# 4ch_GRT_reader.net
KiCad netlist of a schematic drawn in Altium Designer
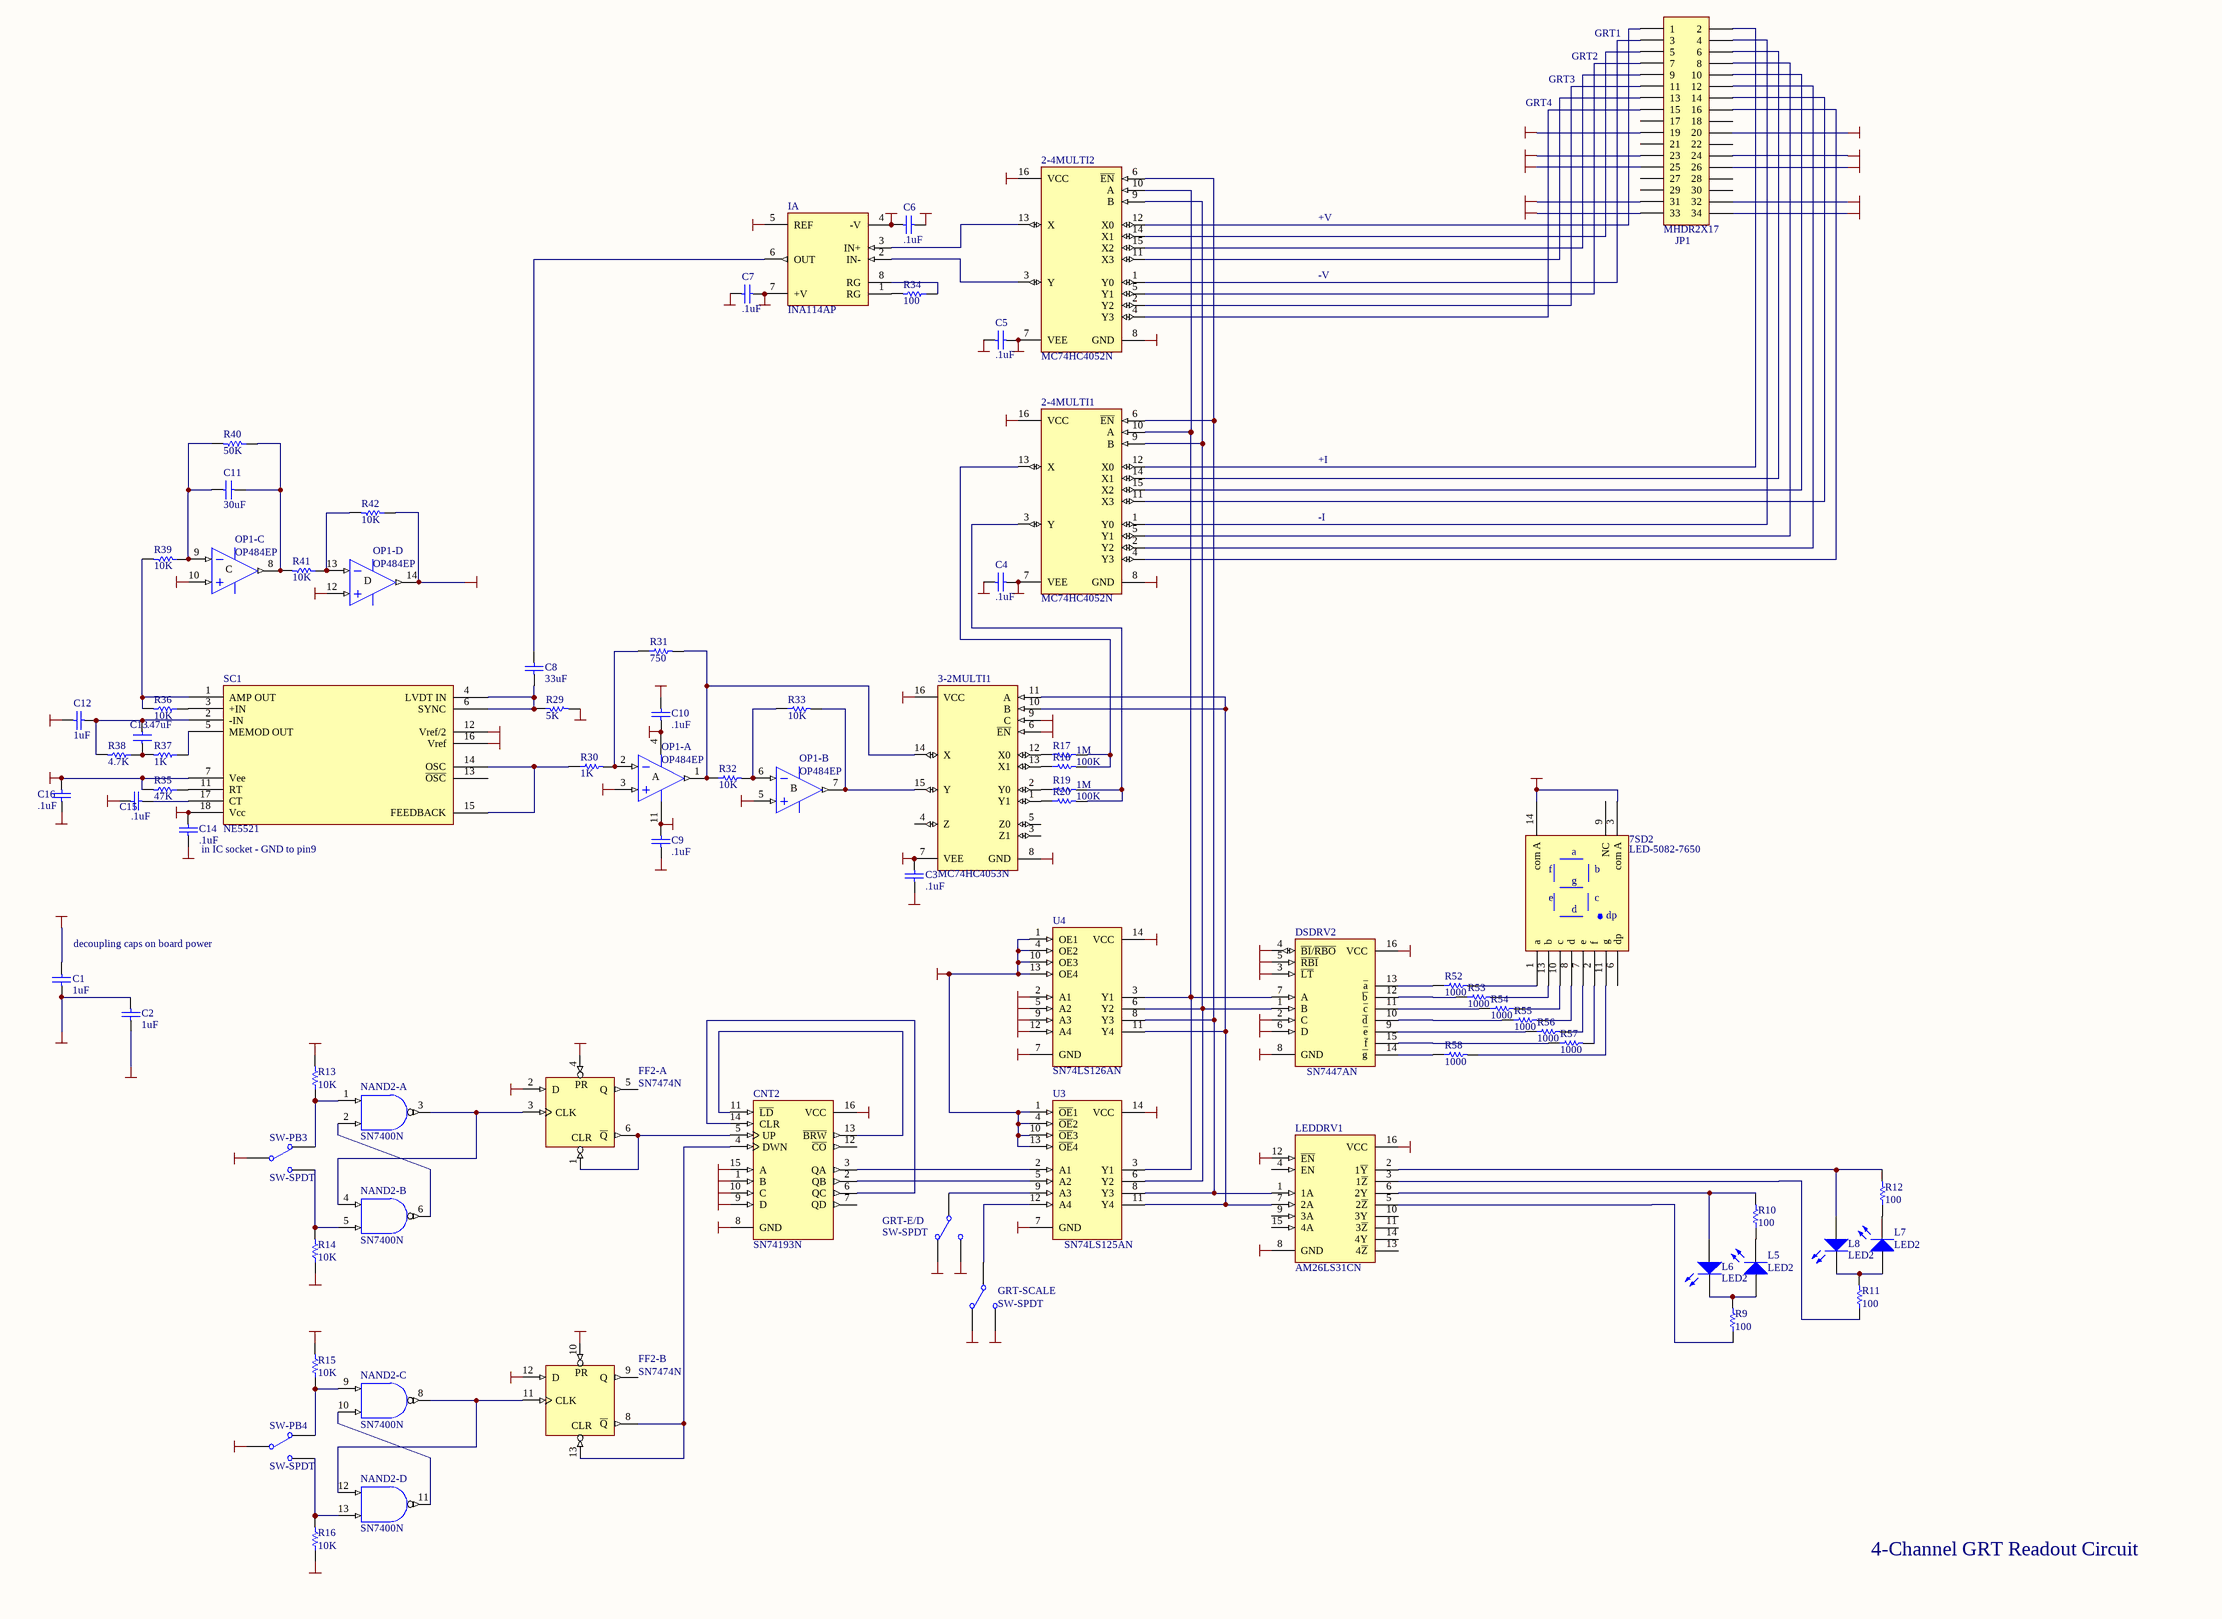
[diagram p0: 4ch GRT reader.SchDoc]

(export (version "E")
  (design (tool "Eeschema 10.0.6"))
  (components
    (comp (ref "2-4MULTI1")
      (value "MC74HC4052N")
      (footprint "DIP-16/X1.5")
      (description "Dual 4-Channel Analog Multiplexer/Demultiplexer")
      (fields (field (name "MANUFACTURER") "ON Semiconductor"))
      (libsource (lib "ON Semi Logic Multiplexer") (part "MC74HC4052N"))
    )
    (comp (ref "2-4MULTI2")
      (value "MC74HC4052N")
      (footprint "DIP-16/X1.5")
      (description "Dual 4-Channel Analog Multiplexer/Demultiplexer")
      (fields (field (name "MANUFACTURER") "ON Semiconductor"))
      (libsource (lib "ON Semi Logic Multiplexer") (part "MC74HC4052N"))
    )
    (comp (ref "3-2MULTI1")
      (value "MC74HC4053N")
      (footprint "DIP-16/X1.5")
      (description "Analog Multiplexer/Demultiplexer")
      (fields (field (name "MANUFACTURER") "ON Semiconductor"))
      (libsource (lib "ON Semi Logic Multiplexer") (part "MC74HC4053N"))
    )
    (comp (ref "7SD2")
      (value "LED-5082-7650")
      (footprint "DIP-14")
      (libsource (lib "Steves Integrated Library1") (part "LED-5082-7650"))
    )
    (comp (ref "C1")
      (value "1uF")
      (footprint "RAD-0.2")
      (description "Capacitor")
      (fields (field (name "MANUFACTURER") "Generic Components") (field (name "ALTIUM_VALUE") "1uF"))
      (libsource (lib "Miscellaneous Devices") (part "Cap"))
    )
    (comp (ref "C2")
      (value "1uF")
      (footprint "RAD-0.2")
      (description "Capacitor")
      (fields (field (name "MANUFACTURER") "Generic Components") (field (name "ALTIUM_VALUE") "1uF"))
      (libsource (lib "Miscellaneous Devices") (part "Cap"))
    )
    (comp (ref "C3")
      (value ".1uF")
      (footprint "RAD-0.1")
      (description "Capacitor")
      (fields (field (name "MANUFACTURER") "Generic Components") (field (name "ALTIUM_VALUE") ".1uF"))
      (libsource (lib "Miscellaneous Devices") (part "Cap"))
    )
    (comp (ref "C4")
      (value ".1uF")
      (footprint "RAD-0.1")
      (description "Capacitor")
      (fields (field (name "MANUFACTURER") "Generic Components") (field (name "ALTIUM_VALUE") ".1uF"))
      (libsource (lib "Miscellaneous Devices") (part "Cap"))
    )
    (comp (ref "C5")
      (value ".1uF")
      (footprint "RAD-0.1")
      (description "Capacitor")
      (fields (field (name "MANUFACTURER") "Generic Components") (field (name "ALTIUM_VALUE") ".1uF"))
      (libsource (lib "Miscellaneous Devices") (part "Cap"))
    )
    (comp (ref "C6")
      (value ".1uF")
      (footprint "RAD-0.1")
      (description "Capacitor")
      (fields (field (name "MANUFACTURER") "Generic Components") (field (name "ALTIUM_VALUE") ".1uF"))
      (libsource (lib "Miscellaneous Devices") (part "Cap"))
    )
    (comp (ref "C7")
      (value ".1uF")
      (footprint "RAD-0.1")
      (description "Capacitor")
      (fields (field (name "MANUFACTURER") "Generic Components") (field (name "ALTIUM_VALUE") ".1uF"))
      (libsource (lib "Miscellaneous Devices") (part "Cap"))
    )
    (comp (ref "C8")
      (value "33uF")
      (footprint "RAD-0.1")
      (description "Capacitor")
      (fields (field (name "MANUFACTURER") "Generic Components") (field (name "ALTIUM_VALUE") "33uF"))
      (libsource (lib "Miscellaneous Devices") (part "Cap"))
    )
    (comp (ref "C9")
      (value ".1uF")
      (footprint "RAD-0.1")
      (description "Capacitor")
      (fields (field (name "MANUFACTURER") "Generic Components") (field (name "ALTIUM_VALUE") ".1uF"))
      (libsource (lib "Miscellaneous Devices") (part "Cap"))
    )
    (comp (ref "C10")
      (value ".1uF")
      (footprint "RAD-0.1")
      (description "Capacitor")
      (fields (field (name "MANUFACTURER") "Generic Components") (field (name "ALTIUM_VALUE") ".1uF"))
      (libsource (lib "Miscellaneous Devices") (part "Cap"))
    )
    (comp (ref "C11")
      (value "30uF")
      (footprint "RAD-0.1")
      (description "Capacitor")
      (fields (field (name "MANUFACTURER") "Generic Components") (field (name "ALTIUM_VALUE") "30uF"))
      (libsource (lib "Miscellaneous Devices") (part "Cap"))
    )
    (comp (ref "C12")
      (value "1uF")
      (footprint "RAD-0.1")
      (description "Capacitor")
      (fields (field (name "MANUFACTURER") "Generic Components") (field (name "ALTIUM_VALUE") "1uF"))
      (libsource (lib "") (part "Cap_1"))
    )
    (comp (ref "C13")
      (value ".47uF")
      (footprint "RAD-0.1")
      (description "Capacitor")
      (fields (field (name "MANUFACTURER") "Generic Components") (field (name "ALTIUM_VALUE") ".47uF"))
      (libsource (lib "Miscellaneous Devices") (part "Cap"))
    )
    (comp (ref "C14")
      (value "in IC socket - GND to pin9")
      (footprint "RAD-0.1")
      (description "Capacitor")
      (fields (field (name "MANUFACTURER") "Generic Components") (field (name "ALTIUM_VALUE") ".1uF"))
      (libsource (lib "Miscellaneous Devices") (part "Cap"))
    )
    (comp (ref "C15")
      (value ".1uF")
      (footprint "RAD-0.1")
      (description "Capacitor")
      (fields (field (name "MANUFACTURER") "Generic Components") (field (name "ALTIUM_VALUE") ".1uF"))
      (libsource (lib "Miscellaneous Devices") (part "Cap"))
    )
    (comp (ref "C16")
      (value ".1uF")
      (footprint "RAD-0.1")
      (description "Capacitor")
      (fields (field (name "MANUFACTURER") "Generic Components") (field (name "ALTIUM_VALUE") ".1uF"))
      (libsource (lib "Miscellaneous Devices") (part "Cap"))
    )
    (comp (ref "CNT2")
      (value "SN74193N")
      (footprint "DIP-16/X1.5")
      (description "Synchronous 4-Bit Up/Down Counter (Dual Clock with Clear)")
      (fields (field (name "MANUFACTURER") "Texas Instruments"))
      (libsource (lib "TI Logic Counter") (part "SN74193N"))
    )
    (comp (ref "DSDRV2")
      (value "SN7447AN")
      (footprint "DIP-16/X1.5")
      (description "BCD-to-Seven-Segment Decoder/Driver")
      (fields (field (name "MANUFACTURER") "Texas Instruments"))
      (libsource (lib "TI Interface Display Driver") (part "SN7447AN"))
    )
    (comp (ref "FF2-")
      (value "SN7474N")
      (footprint "DIP-14/D19.7")
      (description "Dual D-Type Positive-Edge-Triggered Flip-Flop with Preset and Clear")
      (fields (field (name "MANUFACTURER") "Texas Instruments"))
      (libsource (lib "TI Logic Flip-Flop") (part "SN7474N"))
    )
    (comp (ref "GRT-E/D")
      (value "SW-SPDT")
      (footprint "SPDT-3")
      (description "Single-Pole, Double-Throw Switch")
      (fields (field (name "MANUFACTURER") "Generic Components"))
      (libsource (lib "Miscellaneous Devices") (part "SW-SPDT"))
    )
    (comp (ref "GRT-SCALE")
      (value "SW-SPDT")
      (footprint "SPDT-3")
      (description "Single-Pole, Double-Throw Switch")
      (fields (field (name "MANUFACTURER") "Generic Components"))
      (libsource (lib "Miscellaneous Devices") (part "SW-SPDT"))
    )
    (comp (ref "IA")
      (value "INA114AP")
      (footprint "DIP-8")
      (description "Precision Instrumentation Amplifier")
      (fields (field (name "MANUFACTURER") "Burr-Brown"))
      (libsource (lib "BB Instrumentation Amplifier") (part "INA114AP"))
    )
    (comp (ref "JP1")
      (value "MHDR2X17")
      (footprint "HDR2X17")
      (description "Header, 17-Pin, Dual row")
      (fields (field (name "MANUFACTURER") "Generic Components"))
      (libsource (lib "Miscellaneous Connectors") (part "MHDR2X17"))
    )
    (comp (ref "L5")
      (value "LED2")
      (footprint "HDR1X2")
      (description "Typical RED, GREEN, YELLOW, AMBER GaAs LED")
      (fields (field (name "MANUFACTURER") "Generic Components"))
      (libsource (lib "Miscellaneous Devices") (part "LED2"))
    )
    (comp (ref "L6")
      (value "LED2")
      (footprint "HDR1X2")
      (description "Typical RED, GREEN, YELLOW, AMBER GaAs LED")
      (fields (field (name "MANUFACTURER") "Generic Components"))
      (libsource (lib "Miscellaneous Devices") (part "LED2"))
    )
    (comp (ref "L7")
      (value "LED2")
      (footprint "HDR1X2")
      (description "Typical RED, GREEN, YELLOW, AMBER GaAs LED")
      (fields (field (name "MANUFACTURER") "Generic Components"))
      (libsource (lib "Miscellaneous Devices") (part "LED2"))
    )
    (comp (ref "L8")
      (value "LED2")
      (footprint "HDR1X2")
      (description "Typical RED, GREEN, YELLOW, AMBER GaAs LED")
      (fields (field (name "MANUFACTURER") "Generic Components"))
      (libsource (lib "Miscellaneous Devices") (part "LED2"))
    )
    (comp (ref "LEDDRV1")
      (value "AM26LS31CN")
      (footprint "DIP-16/X1.5")
      (description "Quadruple Differential Line Driver")
      (fields (field (name "MANUFACTURER") "Texas Instruments"))
      (libsource (lib "TI Interface Line Driver") (part "AM26LS31CN"))
    )
    (comp (ref "NAND2-")
      (value "SN7400N")
      (footprint "DIP-14/D19.7")
      (description "Quadruple 2-Input Positive-NAND Gate")
      (fields (field (name "MANUFACTURER") "Texas Instruments"))
      (libsource (lib "TI Logic Gate 1") (part "SN7400N"))
    )
    (comp (ref "OP1-")
      (value "OP484EP")
      (footprint "DIP-14")
      (description "Precision Rail-to-Rail Input and Output Operational Amplifier")
      (fields (field (name "MANUFACTURER") "Analog Devices"))
      (libsource (lib "AD Operational Amplifier") (part "OP484EP"))
    )
    (comp (ref "R9")
      (value "100")
      (footprint "AXIAL-0.3")
      (description "Resistor")
      (fields (field (name "MANUFACTURER") "Generic Components") (field (name "ALTIUM_VALUE") "100"))
      (libsource (lib "Miscellaneous Devices") (part "Res1"))
    )
    (comp (ref "R10")
      (value "100")
      (footprint "AXIAL-0.3")
      (description "Resistor")
      (fields (field (name "MANUFACTURER") "Generic Components") (field (name "ALTIUM_VALUE") "100"))
      (libsource (lib "Miscellaneous Devices") (part "Res1"))
    )
    (comp (ref "R11")
      (value "100")
      (footprint "AXIAL-0.3")
      (description "Resistor")
      (fields (field (name "MANUFACTURER") "Generic Components") (field (name "ALTIUM_VALUE") "100"))
      (libsource (lib "Miscellaneous Devices") (part "Res1"))
    )
    (comp (ref "R12")
      (value "100")
      (footprint "AXIAL-0.3")
      (description "Resistor")
      (fields (field (name "MANUFACTURER") "Generic Components") (field (name "ALTIUM_VALUE") "100"))
      (libsource (lib "Miscellaneous Devices") (part "Res1"))
    )
    (comp (ref "R13")
      (value "10K")
      (footprint "AXIAL-0.3")
      (description "Resistor")
      (fields (field (name "MANUFACTURER") "Generic Components") (field (name "ALTIUM_VALUE") "10K"))
      (libsource (lib "Miscellaneous Devices") (part "Res1"))
    )
    (comp (ref "R14")
      (value "10K")
      (footprint "AXIAL-0.3")
      (description "Resistor")
      (fields (field (name "MANUFACTURER") "Generic Components") (field (name "ALTIUM_VALUE") "10K"))
      (libsource (lib "Miscellaneous Devices") (part "Res1"))
    )
    (comp (ref "R15")
      (value "10K")
      (footprint "AXIAL-0.3")
      (description "Resistor")
      (fields (field (name "MANUFACTURER") "Generic Components") (field (name "ALTIUM_VALUE") "10K"))
      (libsource (lib "Miscellaneous Devices") (part "Res1"))
    )
    (comp (ref "R16")
      (value "10K")
      (footprint "AXIAL-0.3")
      (description "Resistor")
      (fields (field (name "MANUFACTURER") "Generic Components") (field (name "ALTIUM_VALUE") "10K"))
      (libsource (lib "Miscellaneous Devices") (part "Res1"))
    )
    (comp (ref "R17")
      (value "1M")
      (footprint "AXIAL-0.3")
      (description "Resistor")
      (fields (field (name "MANUFACTURER") "Generic Components") (field (name "ALTIUM_VALUE") "1M"))
      (libsource (lib "Miscellaneous Devices") (part "Res1"))
    )
    (comp (ref "R18")
      (value "100K")
      (footprint "AXIAL-0.3")
      (description "Resistor")
      (fields (field (name "MANUFACTURER") "Generic Components") (field (name "ALTIUM_VALUE") "100K"))
      (libsource (lib "Miscellaneous Devices") (part "Res1"))
    )
    (comp (ref "R19")
      (value "1M")
      (footprint "AXIAL-0.3")
      (description "Resistor")
      (fields (field (name "MANUFACTURER") "Generic Components") (field (name "ALTIUM_VALUE") "1M"))
      (libsource (lib "Miscellaneous Devices") (part "Res1"))
    )
    (comp (ref "R20")
      (value "100K")
      (footprint "AXIAL-0.3")
      (description "Resistor")
      (fields (field (name "MANUFACTURER") "Generic Components") (field (name "ALTIUM_VALUE") "100K"))
      (libsource (lib "Miscellaneous Devices") (part "Res1"))
    )
    (comp (ref "R29")
      (value "5K")
      (footprint "AXIAL-0.3")
      (description "Resistor")
      (fields (field (name "MANUFACTURER") "Generic Components") (field (name "ALTIUM_VALUE") "5K"))
      (libsource (lib "") (part "Res1_1"))
    )
    (comp (ref "R30")
      (value "1K")
      (footprint "AXIAL-0.3")
      (description "Resistor")
      (fields (field (name "MANUFACTURER") "Generic Components") (field (name "ALTIUM_VALUE") "1K"))
      (libsource (lib "Miscellaneous Devices") (part "Res1"))
    )
    (comp (ref "R31")
      (value "750")
      (footprint "AXIAL-0.3")
      (description "Resistor")
      (fields (field (name "MANUFACTURER") "Generic Components") (field (name "ALTIUM_VALUE") "750"))
      (libsource (lib "Miscellaneous Devices") (part "Res1"))
    )
    (comp (ref "R32")
      (value "10K")
      (footprint "AXIAL-0.3")
      (description "Resistor")
      (fields (field (name "MANUFACTURER") "Generic Components") (field (name "ALTIUM_VALUE") "10K"))
      (libsource (lib "Miscellaneous Devices") (part "Res1"))
    )
    (comp (ref "R33")
      (value "10K")
      (footprint "AXIAL-0.3")
      (description "Resistor")
      (fields (field (name "MANUFACTURER") "Generic Components") (field (name "ALTIUM_VALUE") "10K"))
      (libsource (lib "Miscellaneous Devices") (part "Res1"))
    )
    (comp (ref "R34")
      (value "100")
      (footprint "AXIAL-0.3")
      (description "Resistor")
      (fields (field (name "MANUFACTURER") "Generic Components") (field (name "ALTIUM_VALUE") "100"))
      (libsource (lib "Miscellaneous Devices") (part "Res1"))
    )
    (comp (ref "R35")
      (value "47K")
      (footprint "AXIAL-0.3")
      (description "Resistor")
      (fields (field (name "MANUFACTURER") "Generic Components") (field (name "ALTIUM_VALUE") "47K"))
      (libsource (lib "Miscellaneous Devices") (part "Res1"))
    )
    (comp (ref "R36")
      (value "10K")
      (footprint "AXIAL-0.3")
      (description "Resistor")
      (fields (field (name "MANUFACTURER") "Generic Components") (field (name "ALTIUM_VALUE") "10K"))
      (libsource (lib "") (part "Res1_2"))
    )
    (comp (ref "R37")
      (value "1K")
      (footprint "AXIAL-0.3")
      (description "Resistor")
      (fields (field (name "MANUFACTURER") "Generic Components") (field (name "ALTIUM_VALUE") "1K"))
      (libsource (lib "") (part "Res1_2"))
    )
    (comp (ref "R38")
      (value "4.7K")
      (footprint "AXIAL-0.3")
      (description "Resistor")
      (fields (field (name "MANUFACTURER") "Generic Components") (field (name "ALTIUM_VALUE") "4.7K"))
      (libsource (lib "") (part "Res1_2"))
    )
    (comp (ref "R39")
      (value "10K")
      (footprint "AXIAL-0.3")
      (description "Resistor")
      (fields (field (name "MANUFACTURER") "Generic Components") (field (name "ALTIUM_VALUE") "10K"))
      (libsource (lib "") (part "Res1_2"))
    )
    (comp (ref "R40")
      (value "50K")
      (footprint "AXIAL-0.3")
      (description "Resistor")
      (fields (field (name "MANUFACTURER") "Generic Components") (field (name "ALTIUM_VALUE") "50K"))
      (libsource (lib "") (part "Res1_2"))
    )
    (comp (ref "R41")
      (value "10K")
      (footprint "AXIAL-0.3")
      (description "Resistor")
      (fields (field (name "MANUFACTURER") "Generic Components") (field (name "ALTIUM_VALUE") "10K"))
      (libsource (lib "") (part "Res1_2"))
    )
    (comp (ref "R42")
      (value "10K")
      (footprint "AXIAL-0.3")
      (description "Resistor")
      (fields (field (name "MANUFACTURER") "Generic Components") (field (name "ALTIUM_VALUE") "10K"))
      (libsource (lib "") (part "Res1_2"))
    )
    (comp (ref "R52")
      (value "1000")
      (footprint "AXIAL-0.3")
      (description "Resistor")
      (fields (field (name "MANUFACTURER") "Generic Components") (field (name "ALTIUM_VALUE") "1000"))
      (libsource (lib "Miscellaneous Devices") (part "Res1"))
    )
    (comp (ref "R53")
      (value "1000")
      (footprint "AXIAL-0.3")
      (description "Resistor")
      (fields (field (name "MANUFACTURER") "Generic Components") (field (name "ALTIUM_VALUE") "1000"))
      (libsource (lib "Miscellaneous Devices") (part "Res1"))
    )
    (comp (ref "R54")
      (value "1000")
      (footprint "AXIAL-0.3")
      (description "Resistor")
      (fields (field (name "MANUFACTURER") "Generic Components") (field (name "ALTIUM_VALUE") "1000"))
      (libsource (lib "Miscellaneous Devices") (part "Res1"))
    )
    (comp (ref "R55")
      (value "1000")
      (footprint "AXIAL-0.3")
      (description "Resistor")
      (fields (field (name "MANUFACTURER") "Generic Components") (field (name "ALTIUM_VALUE") "1000"))
      (libsource (lib "Miscellaneous Devices") (part "Res1"))
    )
    (comp (ref "R56")
      (value "1000")
      (footprint "AXIAL-0.3")
      (description "Resistor")
      (fields (field (name "MANUFACTURER") "Generic Components") (field (name "ALTIUM_VALUE") "1000"))
      (libsource (lib "Miscellaneous Devices") (part "Res1"))
    )
    (comp (ref "R57")
      (value "1000")
      (footprint "AXIAL-0.3")
      (description "Resistor")
      (fields (field (name "MANUFACTURER") "Generic Components") (field (name "ALTIUM_VALUE") "1000"))
      (libsource (lib "Miscellaneous Devices") (part "Res1"))
    )
    (comp (ref "R58")
      (value "1000")
      (footprint "AXIAL-0.3")
      (description "Resistor")
      (fields (field (name "MANUFACTURER") "Generic Components") (field (name "ALTIUM_VALUE") "1000"))
      (libsource (lib "Miscellaneous Devices") (part "Res1"))
    )
    (comp (ref "SC1")
      (value "NE5521")
      (footprint "DIP-18")
      (libsource (lib "Steves Integrated Library1") (part "NE5521"))
    )
    (comp (ref "SW-PB3")
      (value "SW-SPDT")
      (footprint "SPDT-3")
      (description "Single-Pole, Double-Throw Switch")
      (fields (field (name "MANUFACTURER") "Generic Components"))
      (libsource (lib "Miscellaneous Devices") (part "SW-SPDT"))
    )
    (comp (ref "SW-PB4")
      (value "SW-SPDT")
      (footprint "SPDT-3")
      (description "Single-Pole, Double-Throw Switch")
      (fields (field (name "MANUFACTURER") "Generic Components"))
      (libsource (lib "Miscellaneous Devices") (part "SW-SPDT"))
    )
    (comp (ref "U3")
      (value "SN74LS125AN")
      (footprint "DIP-14/D19.7")
      (description "Quadruple Bus Buffer with 3-State Outputs")
      (fields (field (name "MANUFACTURER") "Texas Instruments"))
      (libsource (lib "TI Logic Buffer Line Driver") (part "SN74LS125AN"))
    )
    (comp (ref "U4")
      (value "SN74LS126AN")
      (footprint "DIP-14/D19.7")
      (description "Quadruple Bus Buffer with 3-State Outputs")
      (fields (field (name "MANUFACTURER") "Texas Instruments"))
      (libsource (lib "TI Logic Buffer Line Driver") (part "SN74LS126AN"))
    )
  )
  (nets
    (net (code "1") (name "+5V") (class "Default")
      (node (ref "2-4MULTI1") (pin "16") (pinfunction "VCC_16") (pintype "power_in"))
      (node (ref "2-4MULTI2") (pin "16") (pinfunction "VCC_16") (pintype "power_in"))
      (node (ref "3-2MULTI1") (pin "16") (pinfunction "VCC_16") (pintype "power_in"))
      (node (ref "7SD2") (pin "14") (pinfunction "com_A_14") (pintype "passive"))
      (node (ref "7SD2") (pin "3") (pinfunction "com_A_3") (pintype "passive"))
      (node (ref "C1") (pin "2") (pinfunction "2_2") (pintype "passive"))
      (node (ref "C10") (pin "1") (pinfunction "1_1") (pintype "passive"))
      (node (ref "C14") (pin "2") (pinfunction "2_2") (pintype "passive"))
      (node (ref "C7") (pin "2") (pinfunction "2_2") (pintype "passive"))
      (node (ref "CNT2") (pin "1") (pinfunction "B_1") (pintype "input"))
      (node (ref "CNT2") (pin "15") (pinfunction "A_15") (pintype "input"))
      (node (ref "CNT2") (pin "16") (pinfunction "VCC_16") (pintype "power_in"))
      (node (ref "DSDRV2") (pin "16") (pinfunction "VCC_16") (pintype "power_in"))
      (node (ref "DSDRV2") (pin "3") (pinfunction "~{LT}_3") (pintype "input"))
      (node (ref "DSDRV2") (pin "4") (pinfunction "~{BI}/~{RBO}_4") (pintype "bidirectional"))
      (node (ref "DSDRV2") (pin "5") (pinfunction "~{RBI}_5") (pintype "input"))
      (node (ref "FF2-") (pin "10") (pinfunction "PR_10") (pintype "input"))
      (node (ref "FF2-") (pin "12") (pinfunction "D_12") (pintype "input"))
      (node (ref "FF2-") (pin "2") (pinfunction "D_2") (pintype "input"))
      (node (ref "FF2-") (pin "4") (pinfunction "PR_4") (pintype "input"))
      (node (ref "GRT-E/D") (pin "2") (pinfunction "NC_2") (pintype "passive"))
      (node (ref "GRT-SCALE") (pin "2") (pinfunction "NC_2") (pintype "passive"))
      (node (ref "IA") (pin "7") (pinfunction "+V_7") (pintype "power_in"))
      (node (ref "JP1") (pin "23") (pinfunction "23_23") (pintype "passive"))
      (node (ref "LEDDRV1") (pin "16") (pinfunction "VCC_16") (pintype "power_in"))
      (node (ref "OP1-") (pin "4") (pinfunction "V+_4") (pintype "power_in"))
      (node (ref "R13") (pin "2") (pinfunction "2_2") (pintype "passive"))
      (node (ref "R14") (pin "1") (pinfunction "1_1") (pintype "passive"))
      (node (ref "R15") (pin "2") (pinfunction "2_2") (pintype "passive"))
      (node (ref "R16") (pin "1") (pinfunction "1_1") (pintype "passive"))
      (node (ref "SC1") (pin "16") (pinfunction "Vref_16") (pintype "passive"))
      (node (ref "SC1") (pin "18") (pinfunction "Vcc_18") (pintype "passive"))
      (node (ref "U3") (pin "14") (pinfunction "VCC_14") (pintype "power_in"))
      (node (ref "U4") (pin "14") (pinfunction "VCC_14") (pintype "power_in"))
    )
    (net (code "2") (name "-5V") (class "Default")
      (node (ref "2-4MULTI1") (pin "7") (pinfunction "VEE_7") (pintype "power_in"))
      (node (ref "2-4MULTI2") (pin "7") (pinfunction "VEE_7") (pintype "power_in"))
      (node (ref "3-2MULTI1") (pin "7") (pinfunction "VEE_7") (pintype "power_in"))
      (node (ref "C16") (pin "2") (pinfunction "2_2") (pintype "passive"))
      (node (ref "C2") (pin "1") (pinfunction "1_1") (pintype "passive"))
      (node (ref "C3") (pin "1") (pinfunction "1_1") (pintype "passive"))
      (node (ref "C4") (pin "2") (pinfunction "2_2") (pintype "passive"))
      (node (ref "C5") (pin "2") (pinfunction "2_2") (pintype "passive"))
      (node (ref "C6") (pin "1") (pinfunction "1_1") (pintype "passive"))
      (node (ref "C9") (pin "2") (pinfunction "2_2") (pintype "passive"))
      (node (ref "IA") (pin "4") (pinfunction "-V_4") (pintype "power_in"))
      (node (ref "JP1") (pin "24") (pinfunction "24_24") (pintype "passive"))
      (node (ref "OP1-") (pin "11") (pinfunction "V-_11") (pintype "power_in"))
      (node (ref "R35") (pin "2") (pinfunction "2_2") (pintype "passive"))
      (node (ref "SC1") (pin "7") (pinfunction "Vee_7") (pintype "passive"))
    )
    (net (code "3") (name "DIO0") (class "Default")
      (node (ref "JP1") (pin "31") (pinfunction "31_31") (pintype "passive"))
      (node (ref "U4") (pin "2") (pinfunction "A1_2") (pintype "input"))
    )
    (net (code "4") (name "DIO1") (class "Default")
      (node (ref "JP1") (pin "32") (pinfunction "32_32") (pintype "passive"))
      (node (ref "U4") (pin "5") (pinfunction "A2_5") (pintype "input"))
    )
    (net (code "5") (name "DIO2") (class "Default")
      (node (ref "JP1") (pin "33") (pinfunction "33_33") (pintype "passive"))
      (node (ref "U4") (pin "9") (pinfunction "A3_9") (pintype "input"))
    )
    (net (code "6") (name "DIO3") (class "Default")
      (node (ref "JP1") (pin "34") (pinfunction "34_34") (pintype "passive"))
      (node (ref "U4") (pin "12") (pinfunction "A4_12") (pintype "input"))
    )
    (net (code "7") (name "GND") (class "Default")
      (node (ref "2-4MULTI1") (pin "8") (pinfunction "GND_8") (pintype "power_in"))
      (node (ref "2-4MULTI2") (pin "8") (pinfunction "GND_8") (pintype "power_in"))
      (node (ref "3-2MULTI1") (pin "6") (pinfunction "~{EN}_6") (pintype "input"))
      (node (ref "3-2MULTI1") (pin "8") (pinfunction "GND_8") (pintype "power_in"))
      (node (ref "3-2MULTI1") (pin "9") (pinfunction "C_9") (pintype "input"))
      (node (ref "C1") (pin "1") (pinfunction "1_1") (pintype "passive"))
      (node (ref "C10") (pin "2") (pinfunction "2_2") (pintype "passive"))
      (node (ref "C12") (pin "1") (pinfunction "1_1") (pintype "passive"))
      (node (ref "C14") (pin "1") (pinfunction "1_1") (pintype "passive"))
      (node (ref "C15") (pin "1") (pinfunction "1_1") (pintype "passive"))
      (node (ref "C16") (pin "1") (pinfunction "1_1") (pintype "passive"))
      (node (ref "C2") (pin "2") (pinfunction "2_2") (pintype "passive"))
      (node (ref "C3") (pin "2") (pinfunction "2_2") (pintype "passive"))
      (node (ref "C4") (pin "1") (pinfunction "1_1") (pintype "passive"))
      (node (ref "C5") (pin "1") (pinfunction "1_1") (pintype "passive"))
      (node (ref "C6") (pin "2") (pinfunction "2_2") (pintype "passive"))
      (node (ref "C7") (pin "1") (pinfunction "1_1") (pintype "passive"))
      (node (ref "C9") (pin "1") (pinfunction "1_1") (pintype "passive"))
      (node (ref "CNT2") (pin "10") (pinfunction "C_10") (pintype "input"))
      (node (ref "CNT2") (pin "8") (pinfunction "GND_8") (pintype "power_in"))
      (node (ref "CNT2") (pin "9") (pinfunction "D_9") (pintype "input"))
      (node (ref "DSDRV2") (pin "2") (pinfunction "C_2") (pintype "input"))
      (node (ref "DSDRV2") (pin "6") (pinfunction "D_6") (pintype "input"))
      (node (ref "DSDRV2") (pin "8") (pinfunction "GND_8") (pintype "power_in"))
      (node (ref "FF2-") (pin "7") (pinfunction "GND_7") (pintype "power_in"))
      (node (ref "GRT-E/D") (pin "3") (pinfunction "NO_3") (pintype "passive"))
      (node (ref "GRT-SCALE") (pin "3") (pinfunction "NO_3") (pintype "passive"))
      (node (ref "IA") (pin "5") (pinfunction "REF_5") (pintype "passive"))
      (node (ref "JP1") (pin "25") (pinfunction "25_25") (pintype "passive"))
      (node (ref "LEDDRV1") (pin "12") (pinfunction "~{EN}_12") (pintype "input"))
      (node (ref "LEDDRV1") (pin "8") (pinfunction "GND_8") (pintype "power_in"))
      (node (ref "NAND2-") (pin "7") (pinfunction "GND_7") (pintype "power_in"))
      (node (ref "OP1-") (pin "10") (pinfunction "IN+_10") (pintype "input"))
      (node (ref "OP1-") (pin "12") (pinfunction "IN+_12") (pintype "input"))
      (node (ref "OP1-") (pin "3") (pinfunction "IN+_3") (pintype "input"))
      (node (ref "OP1-") (pin "5") (pinfunction "IN+_5") (pintype "input"))
      (node (ref "R29") (pin "2") (pinfunction "2_2") (pintype "passive"))
      (node (ref "SC1") (pin "12") (pinfunction "Vref/2_12") (pintype "passive"))
      (node (ref "SW-PB3") (pin "1") (pinfunction "COMMON_1") (pintype "passive"))
      (node (ref "SW-PB4") (pin "1") (pinfunction "COMMON_1") (pintype "passive"))
      (node (ref "U3") (pin "7") (pinfunction "GND_7") (pintype "power_in"))
      (node (ref "U4") (pin "7") (pinfunction "GND_7") (pintype "power_in"))
    )
    (net (code "8") (name "GRT OUT") (class "Default")
      (node (ref "JP1") (pin "19") (pinfunction "19_19") (pintype "passive"))
      (node (ref "JP1") (pin "20") (pinfunction "20_20") (pintype "passive"))
      (node (ref "OP1-") (pin "14") (pinfunction "OUT_14") (pintype "output"))
      (node (ref "R42") (pin "1") (pinfunction "1_1") (pintype "passive"))
    )
    (net (code "9") (name "L{slash}R Line") (class "Default")
      (node (ref "JP1") (pin "26") (pinfunction "26_26") (pintype "passive"))
      (node (ref "U3") (pin "1") (pinfunction "~{OE}1_1") (pintype "input"))
      (node (ref "U3") (pin "10") (pinfunction "~{OE}3_10") (pintype "input"))
      (node (ref "U3") (pin "13") (pinfunction "~{OE}4_13") (pintype "input"))
      (node (ref "U3") (pin "4") (pinfunction "~{OE}2_4") (pintype "input"))
      (node (ref "U4") (pin "1") (pinfunction "OE1_1") (pintype "input"))
      (node (ref "U4") (pin "10") (pinfunction "OE3_10") (pintype "input"))
      (node (ref "U4") (pin "13") (pinfunction "OE4_13") (pintype "input"))
      (node (ref "U4") (pin "4") (pinfunction "OE2_4") (pintype "input"))
    )
    (net (code "10") (name "Net-(2-4MULTI1-A)") (class "Default")
      (node (ref "2-4MULTI1") (pin "10") (pinfunction "A_10") (pintype "input"))
      (node (ref "2-4MULTI2") (pin "10") (pinfunction "A_10") (pintype "input"))
      (node (ref "DSDRV2") (pin "7") (pinfunction "A_7") (pintype "input"))
      (node (ref "U3") (pin "3") (pinfunction "Y1_3") (pintype "tri_state"))
      (node (ref "U4") (pin "3") (pinfunction "Y1_3") (pintype "tri_state"))
    )
    (net (code "11") (name "Net-(2-4MULTI1-B)") (class "Default")
      (node (ref "2-4MULTI1") (pin "9") (pinfunction "B_9") (pintype "input"))
      (node (ref "2-4MULTI2") (pin "9") (pinfunction "B_9") (pintype "input"))
      (node (ref "DSDRV2") (pin "1") (pinfunction "B_1") (pintype "input"))
      (node (ref "U3") (pin "6") (pinfunction "Y2_6") (pintype "tri_state"))
      (node (ref "U4") (pin "6") (pinfunction "Y2_6") (pintype "tri_state"))
    )
    (net (code "12") (name "Net-(2-4MULTI1-X)") (class "Default")
      (node (ref "2-4MULTI1") (pin "13") (pinfunction "X_13") (pintype "bidirectional"))
      (node (ref "R17") (pin "2") (pinfunction "2_2") (pintype "passive"))
      (node (ref "R18") (pin "2") (pinfunction "2_2") (pintype "passive"))
    )
    (net (code "13") (name "Net-(2-4MULTI1-X0)") (class "Default")
      (node (ref "2-4MULTI1") (pin "12") (pinfunction "X0_12") (pintype "bidirectional"))
      (node (ref "JP1") (pin "2") (pinfunction "2_2") (pintype "passive"))
    )
    (net (code "14") (name "Net-(2-4MULTI1-X1)") (class "Default")
      (node (ref "2-4MULTI1") (pin "14") (pinfunction "X1_14") (pintype "bidirectional"))
      (node (ref "JP1") (pin "6") (pinfunction "6_6") (pintype "passive"))
    )
    (net (code "15") (name "Net-(2-4MULTI1-X2)") (class "Default")
      (node (ref "2-4MULTI1") (pin "15") (pinfunction "X2_15") (pintype "bidirectional"))
      (node (ref "JP1") (pin "10") (pinfunction "10_10") (pintype "passive"))
    )
    (net (code "16") (name "Net-(2-4MULTI1-X3)") (class "Default")
      (node (ref "2-4MULTI1") (pin "11") (pinfunction "X3_11") (pintype "bidirectional"))
      (node (ref "JP1") (pin "14") (pinfunction "14_14") (pintype "passive"))
    )
    (net (code "17") (name "Net-(2-4MULTI1-Y)") (class "Default")
      (node (ref "2-4MULTI1") (pin "3") (pinfunction "Y_3") (pintype "bidirectional"))
      (node (ref "R19") (pin "2") (pinfunction "2_2") (pintype "passive"))
      (node (ref "R20") (pin "2") (pinfunction "2_2") (pintype "passive"))
    )
    (net (code "18") (name "Net-(2-4MULTI1-Y0)") (class "Default")
      (node (ref "2-4MULTI1") (pin "1") (pinfunction "Y0_1") (pintype "bidirectional"))
      (node (ref "JP1") (pin "4") (pinfunction "4_4") (pintype "passive"))
    )
    (net (code "19") (name "Net-(2-4MULTI1-Y1)") (class "Default")
      (node (ref "2-4MULTI1") (pin "5") (pinfunction "Y1_5") (pintype "bidirectional"))
      (node (ref "JP1") (pin "8") (pinfunction "8_8") (pintype "passive"))
    )
    (net (code "20") (name "Net-(2-4MULTI1-Y2)") (class "Default")
      (node (ref "2-4MULTI1") (pin "2") (pinfunction "Y2_2") (pintype "bidirectional"))
      (node (ref "JP1") (pin "12") (pinfunction "12_12") (pintype "passive"))
    )
    (net (code "21") (name "Net-(2-4MULTI1-Y3)") (class "Default")
      (node (ref "2-4MULTI1") (pin "4") (pinfunction "Y3_4") (pintype "bidirectional"))
      (node (ref "JP1") (pin "16") (pinfunction "16_16") (pintype "passive"))
    )
    (net (code "22") (name "Net-(2-4MULTI1-~{EN})") (class "Default")
      (node (ref "2-4MULTI1") (pin "6") (pinfunction "~{EN}_6") (pintype "input"))
      (node (ref "2-4MULTI2") (pin "6") (pinfunction "~{EN}_6") (pintype "input"))
      (node (ref "LEDDRV1") (pin "1") (pinfunction "1A_1") (pintype "input"))
      (node (ref "U3") (pin "8") (pinfunction "Y3_8") (pintype "tri_state"))
      (node (ref "U4") (pin "8") (pinfunction "Y3_8") (pintype "tri_state"))
    )
    (net (code "23") (name "Net-(2-4MULTI2-X)") (class "Default")
      (node (ref "2-4MULTI2") (pin "13") (pinfunction "X_13") (pintype "bidirectional"))
      (node (ref "IA") (pin "3") (pinfunction "IN+_3") (pintype "input"))
    )
    (net (code "24") (name "Net-(2-4MULTI2-X0)") (class "Default")
      (node (ref "2-4MULTI2") (pin "12") (pinfunction "X0_12") (pintype "bidirectional"))
      (node (ref "JP1") (pin "1") (pinfunction "1_1") (pintype "passive"))
    )
    (net (code "25") (name "Net-(2-4MULTI2-X1)") (class "Default")
      (node (ref "2-4MULTI2") (pin "14") (pinfunction "X1_14") (pintype "bidirectional"))
      (node (ref "JP1") (pin "5") (pinfunction "5_5") (pintype "passive"))
    )
    (net (code "26") (name "Net-(2-4MULTI2-X2)") (class "Default")
      (node (ref "2-4MULTI2") (pin "15") (pinfunction "X2_15") (pintype "bidirectional"))
      (node (ref "JP1") (pin "9") (pinfunction "9_9") (pintype "passive"))
    )
    (net (code "27") (name "Net-(2-4MULTI2-X3)") (class "Default")
      (node (ref "2-4MULTI2") (pin "11") (pinfunction "X3_11") (pintype "bidirectional"))
      (node (ref "JP1") (pin "13") (pinfunction "13_13") (pintype "passive"))
    )
    (net (code "28") (name "Net-(2-4MULTI2-Y)") (class "Default")
      (node (ref "2-4MULTI2") (pin "3") (pinfunction "Y_3") (pintype "bidirectional"))
      (node (ref "IA") (pin "2") (pinfunction "IN-_2") (pintype "input"))
    )
    (net (code "29") (name "Net-(2-4MULTI2-Y0)") (class "Default")
      (node (ref "2-4MULTI2") (pin "1") (pinfunction "Y0_1") (pintype "bidirectional"))
      (node (ref "JP1") (pin "3") (pinfunction "3_3") (pintype "passive"))
    )
    (net (code "30") (name "Net-(2-4MULTI2-Y1)") (class "Default")
      (node (ref "2-4MULTI2") (pin "5") (pinfunction "Y1_5") (pintype "bidirectional"))
      (node (ref "JP1") (pin "7") (pinfunction "7_7") (pintype "passive"))
    )
    (net (code "31") (name "Net-(2-4MULTI2-Y2)") (class "Default")
      (node (ref "2-4MULTI2") (pin "2") (pinfunction "Y2_2") (pintype "bidirectional"))
      (node (ref "JP1") (pin "11") (pinfunction "11_11") (pintype "passive"))
    )
    (net (code "32") (name "Net-(2-4MULTI2-Y3)") (class "Default")
      (node (ref "2-4MULTI2") (pin "4") (pinfunction "Y3_4") (pintype "bidirectional"))
      (node (ref "JP1") (pin "15") (pinfunction "15_15") (pintype "passive"))
    )
    (net (code "33") (name "Net-(3-2MULTI1-A)") (class "Default")
      (node (ref "3-2MULTI1") (pin "10") (pinfunction "B_10") (pintype "input"))
      (node (ref "3-2MULTI1") (pin "11") (pinfunction "A_11") (pintype "input"))
      (node (ref "LEDDRV1") (pin "7") (pinfunction "2A_7") (pintype "input"))
      (node (ref "U3") (pin "11") (pinfunction "Y4_11") (pintype "tri_state"))
      (node (ref "U4") (pin "11") (pinfunction "Y4_11") (pintype "tri_state"))
    )
    (net (code "34") (name "Net-(3-2MULTI1-X)") (class "Default")
      (node (ref "3-2MULTI1") (pin "14") (pinfunction "X_14") (pintype "bidirectional"))
      (node (ref "OP1-") (pin "1") (pinfunction "OUT_1") (pintype "output"))
      (node (ref "R31") (pin "2") (pinfunction "2_2") (pintype "passive"))
      (node (ref "R32") (pin "1") (pinfunction "1_1") (pintype "passive"))
    )
    (net (code "35") (name "Net-(3-2MULTI1-X0)") (class "Default")
      (node (ref "3-2MULTI1") (pin "12") (pinfunction "X0_12") (pintype "bidirectional"))
      (node (ref "R17") (pin "1") (pinfunction "1_1") (pintype "passive"))
    )
    (net (code "36") (name "Net-(3-2MULTI1-X1)") (class "Default")
      (node (ref "3-2MULTI1") (pin "13") (pinfunction "X1_13") (pintype "bidirectional"))
      (node (ref "R18") (pin "1") (pinfunction "1_1") (pintype "passive"))
    )
    (net (code "37") (name "Net-(3-2MULTI1-Y)") (class "Default")
      (node (ref "3-2MULTI1") (pin "15") (pinfunction "Y_15") (pintype "bidirectional"))
      (node (ref "OP1-") (pin "7") (pinfunction "OUT_7") (pintype "output"))
      (node (ref "R33") (pin "2") (pinfunction "2_2") (pintype "passive"))
    )
    (net (code "38") (name "Net-(3-2MULTI1-Y0)") (class "Default")
      (node (ref "3-2MULTI1") (pin "2") (pinfunction "Y0_2") (pintype "bidirectional"))
      (node (ref "R19") (pin "1") (pinfunction "1_1") (pintype "passive"))
    )
    (net (code "39") (name "Net-(3-2MULTI1-Y1)") (class "Default")
      (node (ref "3-2MULTI1") (pin "1") (pinfunction "Y1_1") (pintype "bidirectional"))
      (node (ref "R20") (pin "1") (pinfunction "1_1") (pintype "passive"))
    )
    (net (code "40") (name "Net-(7SD2-a)") (class "Default")
      (node (ref "7SD2") (pin "1") (pinfunction "a_1") (pintype "passive"))
      (node (ref "R52") (pin "2") (pinfunction "2_2") (pintype "passive"))
    )
    (net (code "41") (name "Net-(7SD2-b)") (class "Default")
      (node (ref "7SD2") (pin "13") (pinfunction "b_13") (pintype "passive"))
      (node (ref "R53") (pin "2") (pinfunction "2_2") (pintype "passive"))
    )
    (net (code "42") (name "Net-(7SD2-c)") (class "Default")
      (node (ref "7SD2") (pin "10") (pinfunction "c_10") (pintype "passive"))
      (node (ref "R54") (pin "2") (pinfunction "2_2") (pintype "passive"))
    )
    (net (code "43") (name "Net-(7SD2-d)") (class "Default")
      (node (ref "7SD2") (pin "8") (pinfunction "d_8") (pintype "passive"))
      (node (ref "R55") (pin "2") (pinfunction "2_2") (pintype "passive"))
    )
    (net (code "44") (name "Net-(7SD2-e)") (class "Default")
      (node (ref "7SD2") (pin "7") (pinfunction "e_7") (pintype "passive"))
      (node (ref "R56") (pin "2") (pinfunction "2_2") (pintype "passive"))
    )
    (net (code "45") (name "Net-(7SD2-f)") (class "Default")
      (node (ref "7SD2") (pin "2") (pinfunction "f_2") (pintype "passive"))
      (node (ref "R57") (pin "2") (pinfunction "2_2") (pintype "passive"))
    )
    (net (code "46") (name "Net-(7SD2-g)") (class "Default")
      (node (ref "7SD2") (pin "11") (pinfunction "g_11") (pintype "passive"))
      (node (ref "R58") (pin "2") (pinfunction "2_2") (pintype "passive"))
    )
    (net (code "47") (name "Net-(C13-Pad1)") (class "Default")
      (node (ref "C13") (pin "1") (pinfunction "1_1") (pintype "passive"))
      (node (ref "R37") (pin "2") (pinfunction "2_2") (pintype "passive"))
      (node (ref "R38") (pin "1") (pinfunction "1_1") (pintype "passive"))
    )
    (net (code "48") (name "Net-(CNT2-CLR)") (class "Default")
      (node (ref "CNT2") (pin "14") (pinfunction "CLR_14") (pintype "input"))
      (node (ref "CNT2") (pin "6") (pinfunction "QC_6") (pintype "output"))
    )
    (net (code "49") (name "Net-(CNT2-DWN)") (class "Default")
      (node (ref "CNT2") (pin "4") (pinfunction "DWN_4") (pintype "input"))
      (node (ref "FF2-") (pin "13") (pinfunction "CLR_13") (pintype "input"))
      (node (ref "FF2-") (pin "8") (pinfunction "~{Q}_8") (pintype "output"))
    )
    (net (code "50") (name "Net-(CNT2-QA)") (class "Default")
      (node (ref "CNT2") (pin "3") (pinfunction "QA_3") (pintype "output"))
      (node (ref "U3") (pin "2") (pinfunction "A1_2") (pintype "input"))
    )
    (net (code "51") (name "Net-(CNT2-QB)") (class "Default")
      (node (ref "CNT2") (pin "2") (pinfunction "QB_2") (pintype "output"))
      (node (ref "U3") (pin "5") (pinfunction "A2_5") (pintype "input"))
    )
    (net (code "52") (name "Net-(CNT2-UP)") (class "Default")
      (node (ref "CNT2") (pin "5") (pinfunction "UP_5") (pintype "input"))
      (node (ref "FF2-") (pin "1") (pinfunction "CLR_1") (pintype "input"))
      (node (ref "FF2-") (pin "6") (pinfunction "~{Q}_6") (pintype "output"))
    )
    (net (code "53") (name "Net-(CNT2-~{BRW})") (class "Default")
      (node (ref "CNT2") (pin "11") (pinfunction "~{LD}_11") (pintype "input"))
      (node (ref "CNT2") (pin "13") (pinfunction "~{BRW}_13") (pintype "output"))
    )
    (net (code "54") (name "Net-(DSDRV2-~{a})") (class "Default")
      (node (ref "DSDRV2") (pin "13") (pinfunction "~{a}_13") (pintype "open_collector"))
      (node (ref "R52") (pin "1") (pinfunction "1_1") (pintype "passive"))
    )
    (net (code "55") (name "Net-(DSDRV2-~{b})") (class "Default")
      (node (ref "DSDRV2") (pin "12") (pinfunction "~{b}_12") (pintype "open_collector"))
      (node (ref "R53") (pin "1") (pinfunction "1_1") (pintype "passive"))
    )
    (net (code "56") (name "Net-(DSDRV2-~{c})") (class "Default")
      (node (ref "DSDRV2") (pin "11") (pinfunction "~{c}_11") (pintype "open_collector"))
      (node (ref "R54") (pin "1") (pinfunction "1_1") (pintype "passive"))
    )
    (net (code "57") (name "Net-(DSDRV2-~{d})") (class "Default")
      (node (ref "DSDRV2") (pin "10") (pinfunction "~{d}_10") (pintype "open_collector"))
      (node (ref "R55") (pin "1") (pinfunction "1_1") (pintype "passive"))
    )
    (net (code "58") (name "Net-(DSDRV2-~{e})") (class "Default")
      (node (ref "DSDRV2") (pin "9") (pinfunction "~{e}_9") (pintype "open_collector"))
      (node (ref "R56") (pin "1") (pinfunction "1_1") (pintype "passive"))
    )
    (net (code "59") (name "Net-(DSDRV2-~{f})") (class "Default")
      (node (ref "DSDRV2") (pin "15") (pinfunction "~{f}_15") (pintype "open_collector"))
      (node (ref "R57") (pin "1") (pinfunction "1_1") (pintype "passive"))
    )
    (net (code "60") (name "Net-(DSDRV2-~{g})") (class "Default")
      (node (ref "DSDRV2") (pin "14") (pinfunction "~{g}_14") (pintype "open_collector"))
      (node (ref "R58") (pin "1") (pinfunction "1_1") (pintype "passive"))
    )
    (net (code "61") (name "Net-(FF2-A-CLK)") (class "Default")
      (node (ref "FF2-") (pin "3") (pinfunction "CLK_3") (pintype "input"))
      (node (ref "NAND2-") (pin "3") (pinfunction "Y_3") (pintype "output"))
      (node (ref "NAND2-") (pin "4") (pinfunction "A_4") (pintype "input"))
    )
    (net (code "62") (name "Net-(FF2-B-CLK)") (class "Default")
      (node (ref "FF2-") (pin "11") (pinfunction "CLK_11") (pintype "input"))
      (node (ref "NAND2-") (pin "12") (pinfunction "A_12") (pintype "input"))
      (node (ref "NAND2-") (pin "8") (pinfunction "Y_8") (pintype "output"))
    )
    (net (code "63") (name "Net-(GRT-E/D-COMMON)") (class "Default")
      (node (ref "GRT-E/D") (pin "1") (pinfunction "COMMON_1") (pintype "passive"))
      (node (ref "U3") (pin "9") (pinfunction "A3_9") (pintype "input"))
    )
    (net (code "64") (name "Net-(GRT-SCALE-COMMON)") (class "Default")
      (node (ref "GRT-SCALE") (pin "1") (pinfunction "COMMON_1") (pintype "passive"))
      (node (ref "U3") (pin "12") (pinfunction "A4_12") (pintype "input"))
    )
    (net (code "65") (name "Net-(IA-OUT)") (class "Default")
      (node (ref "C8") (pin "2") (pinfunction "2_2") (pintype "passive"))
      (node (ref "IA") (pin "6") (pinfunction "OUT_6") (pintype "output"))
    )
    (net (code "66") (name "Net-(IA-RG-Pad1)") (class "Default")
      (node (ref "IA") (pin "1") (pinfunction "RG_1") (pintype "passive"))
      (node (ref "R34") (pin "2") (pinfunction "2_2") (pintype "passive"))
    )
    (net (code "67") (name "Net-(IA-RG-Pad8)") (class "Default")
      (node (ref "IA") (pin "8") (pinfunction "RG_8") (pintype "passive"))
      (node (ref "R34") (pin "1") (pinfunction "1_1") (pintype "passive"))
    )
    (net (code "68") (name "Net-(L5-A)") (class "Default")
      (node (ref "L5") (pin "1") (pinfunction "A_1") (pintype "passive"))
      (node (ref "L6") (pin "2") (pinfunction "K_2") (pintype "passive"))
      (node (ref "R9") (pin "2") (pinfunction "2_2") (pintype "passive"))
    )
    (net (code "69") (name "Net-(L5-K)") (class "Default")
      (node (ref "L5") (pin "2") (pinfunction "K_2") (pintype "passive"))
      (node (ref "R10") (pin "1") (pinfunction "1_1") (pintype "passive"))
    )
    (net (code "70") (name "Net-(L6-A)") (class "Default")
      (node (ref "L6") (pin "1") (pinfunction "A_1") (pintype "passive"))
      (node (ref "LEDDRV1") (pin "6") (pinfunction "2Y_6") (pintype "tri_state"))
      (node (ref "R10") (pin "2") (pinfunction "2_2") (pintype "passive"))
    )
    (net (code "71") (name "Net-(L7-A)") (class "Default")
      (node (ref "L7") (pin "1") (pinfunction "A_1") (pintype "passive"))
      (node (ref "L8") (pin "2") (pinfunction "K_2") (pintype "passive"))
      (node (ref "R11") (pin "2") (pinfunction "2_2") (pintype "passive"))
    )
    (net (code "72") (name "Net-(L7-K)") (class "Default")
      (node (ref "L7") (pin "2") (pinfunction "K_2") (pintype "passive"))
      (node (ref "R12") (pin "1") (pinfunction "1_1") (pintype "passive"))
    )
    (net (code "73") (name "Net-(L8-A)") (class "Default")
      (node (ref "L8") (pin "1") (pinfunction "A_1") (pintype "passive"))
      (node (ref "LEDDRV1") (pin "2") (pinfunction "1~{Y}_2") (pintype "tri_state"))
      (node (ref "R12") (pin "2") (pinfunction "2_2") (pintype "passive"))
    )
    (net (code "74") (name "Net-(LEDDRV1-1~{Z})") (class "Default")
      (node (ref "LEDDRV1") (pin "3") (pinfunction "1~{Z}_3") (pintype "tri_state"))
      (node (ref "R11") (pin "1") (pinfunction "1_1") (pintype "passive"))
    )
    (net (code "75") (name "Net-(LEDDRV1-2~{Z})") (class "Default")
      (node (ref "LEDDRV1") (pin "5") (pinfunction "2~{Z}_5") (pintype "tri_state"))
      (node (ref "R9") (pin "1") (pinfunction "1_1") (pintype "passive"))
    )
    (net (code "76") (name "Net-(NAND2-A-A)") (class "Default")
      (node (ref "NAND2-") (pin "1") (pinfunction "A_1") (pintype "input"))
      (node (ref "R13") (pin "1") (pinfunction "1_1") (pintype "passive"))
      (node (ref "SW-PB3") (pin "2") (pinfunction "NC_2") (pintype "passive"))
    )
    (net (code "77") (name "Net-(NAND2-A-B)") (class "Default")
      (node (ref "NAND2-") (pin "2") (pinfunction "B_2") (pintype "input"))
      (node (ref "NAND2-") (pin "6") (pinfunction "Y_6") (pintype "output"))
    )
    (net (code "78") (name "Net-(NAND2-B-B)") (class "Default")
      (node (ref "NAND2-") (pin "5") (pinfunction "B_5") (pintype "input"))
      (node (ref "R14") (pin "2") (pinfunction "2_2") (pintype "passive"))
      (node (ref "SW-PB3") (pin "3") (pinfunction "NO_3") (pintype "passive"))
    )
    (net (code "79") (name "Net-(NAND2-C-A)") (class "Default")
      (node (ref "NAND2-") (pin "9") (pinfunction "A_9") (pintype "input"))
      (node (ref "R15") (pin "1") (pinfunction "1_1") (pintype "passive"))
      (node (ref "SW-PB4") (pin "2") (pinfunction "NC_2") (pintype "passive"))
    )
    (net (code "80") (name "Net-(NAND2-C-B)") (class "Default")
      (node (ref "NAND2-") (pin "10") (pinfunction "B_10") (pintype "input"))
      (node (ref "NAND2-") (pin "11") (pinfunction "Y_11") (pintype "output"))
    )
    (net (code "81") (name "Net-(NAND2-D-B)") (class "Default")
      (node (ref "NAND2-") (pin "13") (pinfunction "B_13") (pintype "input"))
      (node (ref "R16") (pin "2") (pinfunction "2_2") (pintype "passive"))
      (node (ref "SW-PB4") (pin "3") (pinfunction "NO_3") (pintype "passive"))
    )
    (net (code "82") (name "Net-(OP1-A-IN-)") (class "Default")
      (node (ref "OP1-") (pin "2") (pinfunction "IN-_2") (pintype "input"))
      (node (ref "R30") (pin "2") (pinfunction "2_2") (pintype "passive"))
      (node (ref "R31") (pin "1") (pinfunction "1_1") (pintype "passive"))
    )
    (net (code "83") (name "Net-(OP1-B-IN-)") (class "Default")
      (node (ref "OP1-") (pin "6") (pinfunction "IN-_6") (pintype "input"))
      (node (ref "R32") (pin "2") (pinfunction "2_2") (pintype "passive"))
      (node (ref "R33") (pin "1") (pinfunction "1_1") (pintype "passive"))
    )
    (net (code "84") (name "Net-(OP1-C-IN-)") (class "Default")
      (node (ref "C11") (pin "1") (pinfunction "1_1") (pintype "passive"))
      (node (ref "OP1-") (pin "9") (pinfunction "IN-_9") (pintype "input"))
      (node (ref "R39") (pin "1") (pinfunction "1_1") (pintype "passive"))
      (node (ref "R40") (pin "2") (pinfunction "2_2") (pintype "passive"))
    )
    (net (code "85") (name "Net-(OP1-C-OUT)") (class "Default")
      (node (ref "C11") (pin "2") (pinfunction "2_2") (pintype "passive"))
      (node (ref "OP1-") (pin "8") (pinfunction "OUT_8") (pintype "output"))
      (node (ref "R40") (pin "1") (pinfunction "1_1") (pintype "passive"))
      (node (ref "R41") (pin "2") (pinfunction "2_2") (pintype "passive"))
    )
    (net (code "86") (name "Net-(OP1-D-IN-)") (class "Default")
      (node (ref "OP1-") (pin "13") (pinfunction "IN-_13") (pintype "input"))
      (node (ref "R41") (pin "1") (pinfunction "1_1") (pintype "passive"))
      (node (ref "R42") (pin "2") (pinfunction "2_2") (pintype "passive"))
    )
    (net (code "87") (name "Net-(SC1-+IN)") (class "Default")
      (node (ref "R36") (pin "1") (pinfunction "1_1") (pintype "passive"))
      (node (ref "SC1") (pin "3") (pinfunction "+IN_3") (pintype "passive"))
    )
    (net (code "88") (name "Net-(SC1--IN)") (class "Default")
      (node (ref "C12") (pin "2") (pinfunction "2_2") (pintype "passive"))
      (node (ref "C13") (pin "2") (pinfunction "2_2") (pintype "passive"))
      (node (ref "R38") (pin "2") (pinfunction "2_2") (pintype "passive"))
      (node (ref "SC1") (pin "2") (pinfunction "-IN_2") (pintype "passive"))
    )
    (net (code "89") (name "Net-(SC1-AMP_OUT)") (class "Default")
      (node (ref "R36") (pin "2") (pinfunction "2_2") (pintype "passive"))
      (node (ref "R39") (pin "2") (pinfunction "2_2") (pintype "passive"))
      (node (ref "SC1") (pin "1") (pinfunction "AMP_OUT_1") (pintype "passive"))
    )
    (net (code "90") (name "Net-(SC1-CT)") (class "Default")
      (node (ref "C15") (pin "2") (pinfunction "2_2") (pintype "passive"))
      (node (ref "SC1") (pin "17") (pinfunction "CT_17") (pintype "passive"))
    )
    (net (code "91") (name "Net-(SC1-FEEDBACK)") (class "Default")
      (node (ref "R30") (pin "1") (pinfunction "1_1") (pintype "passive"))
      (node (ref "SC1") (pin "14") (pinfunction "OSC_14") (pintype "passive"))
      (node (ref "SC1") (pin "15") (pinfunction "FEEDBACK_15") (pintype "passive"))
    )
    (net (code "92") (name "Net-(SC1-LVDT_IN)") (class "Default")
      (node (ref "C8") (pin "1") (pinfunction "1_1") (pintype "passive"))
      (node (ref "R29") (pin "1") (pinfunction "1_1") (pintype "passive"))
      (node (ref "SC1") (pin "4") (pinfunction "LVDT_IN_4") (pintype "passive"))
      (node (ref "SC1") (pin "6") (pinfunction "SYNC_6") (pintype "passive"))
    )
    (net (code "93") (name "Net-(SC1-MEMOD_OUT)") (class "Default")
      (node (ref "R37") (pin "1") (pinfunction "1_1") (pintype "passive"))
      (node (ref "SC1") (pin "5") (pinfunction "MEMOD_OUT_5") (pintype "passive"))
    )
    (net (code "94") (name "Net-(SC1-RT)") (class "Default")
      (node (ref "R35") (pin "1") (pinfunction "1_1") (pintype "passive"))
      (node (ref "SC1") (pin "11") (pinfunction "RT_11") (pintype "passive"))
    )
    (net (code "95") (name "VCC") (class "Default")
      (node (ref "FF2-") (pin "14") (pinfunction "VCC_14") (pintype "power_in"))
      (node (ref "NAND2-") (pin "14") (pinfunction "VCC_14") (pintype "power_in"))
    )
    (net (code "96") (name "unconnected-(3-2MULTI1-Z-Pad4)") (class "Default")
      (node (ref "3-2MULTI1") (pin "4") (pinfunction "Z_4") (pintype "bidirectional"))
    )
    (net (code "97") (name "unconnected-(3-2MULTI1-Z0-Pad5)") (class "Default")
      (node (ref "3-2MULTI1") (pin "5") (pinfunction "Z0_5") (pintype "bidirectional"))
    )
    (net (code "98") (name "unconnected-(3-2MULTI1-Z1-Pad3)") (class "Default")
      (node (ref "3-2MULTI1") (pin "3") (pinfunction "Z1_3") (pintype "bidirectional"))
    )
    (net (code "99") (name "unconnected-(7SD2-NC-Pad9)") (class "Default")
      (node (ref "7SD2") (pin "9") (pinfunction "NC_9") (pintype "passive"))
    )
    (net (code "100") (name "unconnected-(7SD2-dp-Pad6)") (class "Default")
      (node (ref "7SD2") (pin "6") (pinfunction "dp_6") (pintype "passive"))
    )
    (net (code "101") (name "unconnected-(CNT2-QD-Pad7)") (class "Default")
      (node (ref "CNT2") (pin "7") (pinfunction "QD_7") (pintype "output"))
    )
    (net (code "102") (name "unconnected-(CNT2-~{CO}-Pad12)") (class "Default")
      (node (ref "CNT2") (pin "12") (pinfunction "~{CO}_12") (pintype "output"))
    )
    (net (code "103") (name "unconnected-(FF2-A-Q-Pad5)") (class "Default")
      (node (ref "FF2-") (pin "5") (pinfunction "Q_5") (pintype "output"))
    )
    (net (code "104") (name "unconnected-(FF2-B-Q-Pad9)") (class "Default")
      (node (ref "FF2-") (pin "9") (pinfunction "Q_9") (pintype "output"))
    )
    (net (code "105") (name "unconnected-(JP1-Pad17)") (class "Default")
      (node (ref "JP1") (pin "17") (pinfunction "17_17") (pintype "passive"))
    )
    (net (code "106") (name "unconnected-(JP1-Pad18)") (class "Default")
      (node (ref "JP1") (pin "18") (pinfunction "18_18") (pintype "passive"))
    )
    (net (code "107") (name "unconnected-(JP1-Pad21)") (class "Default")
      (node (ref "JP1") (pin "21") (pinfunction "21_21") (pintype "passive"))
    )
    (net (code "108") (name "unconnected-(JP1-Pad22)") (class "Default")
      (node (ref "JP1") (pin "22") (pinfunction "22_22") (pintype "passive"))
    )
    (net (code "109") (name "unconnected-(JP1-Pad27)") (class "Default")
      (node (ref "JP1") (pin "27") (pinfunction "27_27") (pintype "passive"))
    )
    (net (code "110") (name "unconnected-(JP1-Pad28)") (class "Default")
      (node (ref "JP1") (pin "28") (pinfunction "28_28") (pintype "passive"))
    )
    (net (code "111") (name "unconnected-(JP1-Pad29)") (class "Default")
      (node (ref "JP1") (pin "29") (pinfunction "29_29") (pintype "passive"))
    )
    (net (code "112") (name "unconnected-(JP1-Pad30)") (class "Default")
      (node (ref "JP1") (pin "30") (pinfunction "30_30") (pintype "passive"))
    )
    (net (code "113") (name "unconnected-(LEDDRV1-3A-Pad9)") (class "Default")
      (node (ref "LEDDRV1") (pin "9") (pinfunction "3A_9") (pintype "input"))
    )
    (net (code "114") (name "unconnected-(LEDDRV1-3Y-Pad10)") (class "Default")
      (node (ref "LEDDRV1") (pin "10") (pinfunction "3Y_10") (pintype "tri_state"))
    )
    (net (code "115") (name "unconnected-(LEDDRV1-3~{Z}-Pad11)") (class "Default")
      (node (ref "LEDDRV1") (pin "11") (pinfunction "3~{Z}_11") (pintype "tri_state"))
    )
    (net (code "116") (name "unconnected-(LEDDRV1-4A-Pad15)") (class "Default")
      (node (ref "LEDDRV1") (pin "15") (pinfunction "4A_15") (pintype "input"))
    )
    (net (code "117") (name "unconnected-(LEDDRV1-4Y-Pad14)") (class "Default")
      (node (ref "LEDDRV1") (pin "14") (pinfunction "4Y_14") (pintype "tri_state"))
    )
    (net (code "118") (name "unconnected-(LEDDRV1-4~{Z}-Pad13)") (class "Default")
      (node (ref "LEDDRV1") (pin "13") (pinfunction "4~{Z}_13") (pintype "tri_state"))
    )
    (net (code "119") (name "unconnected-(LEDDRV1-EN-Pad4)") (class "Default")
      (node (ref "LEDDRV1") (pin "4") (pinfunction "EN_4") (pintype "input"))
    )
    (net (code "120") (name "unconnected-(SC1-~{OSC}-Pad13)") (class "Default")
      (node (ref "SC1") (pin "13") (pinfunction "~{OSC}_13") (pintype "passive"))
    )
  )
)
